# peripheral_UART.net
KiCad netlist of a schematic drawn in Altium Designer
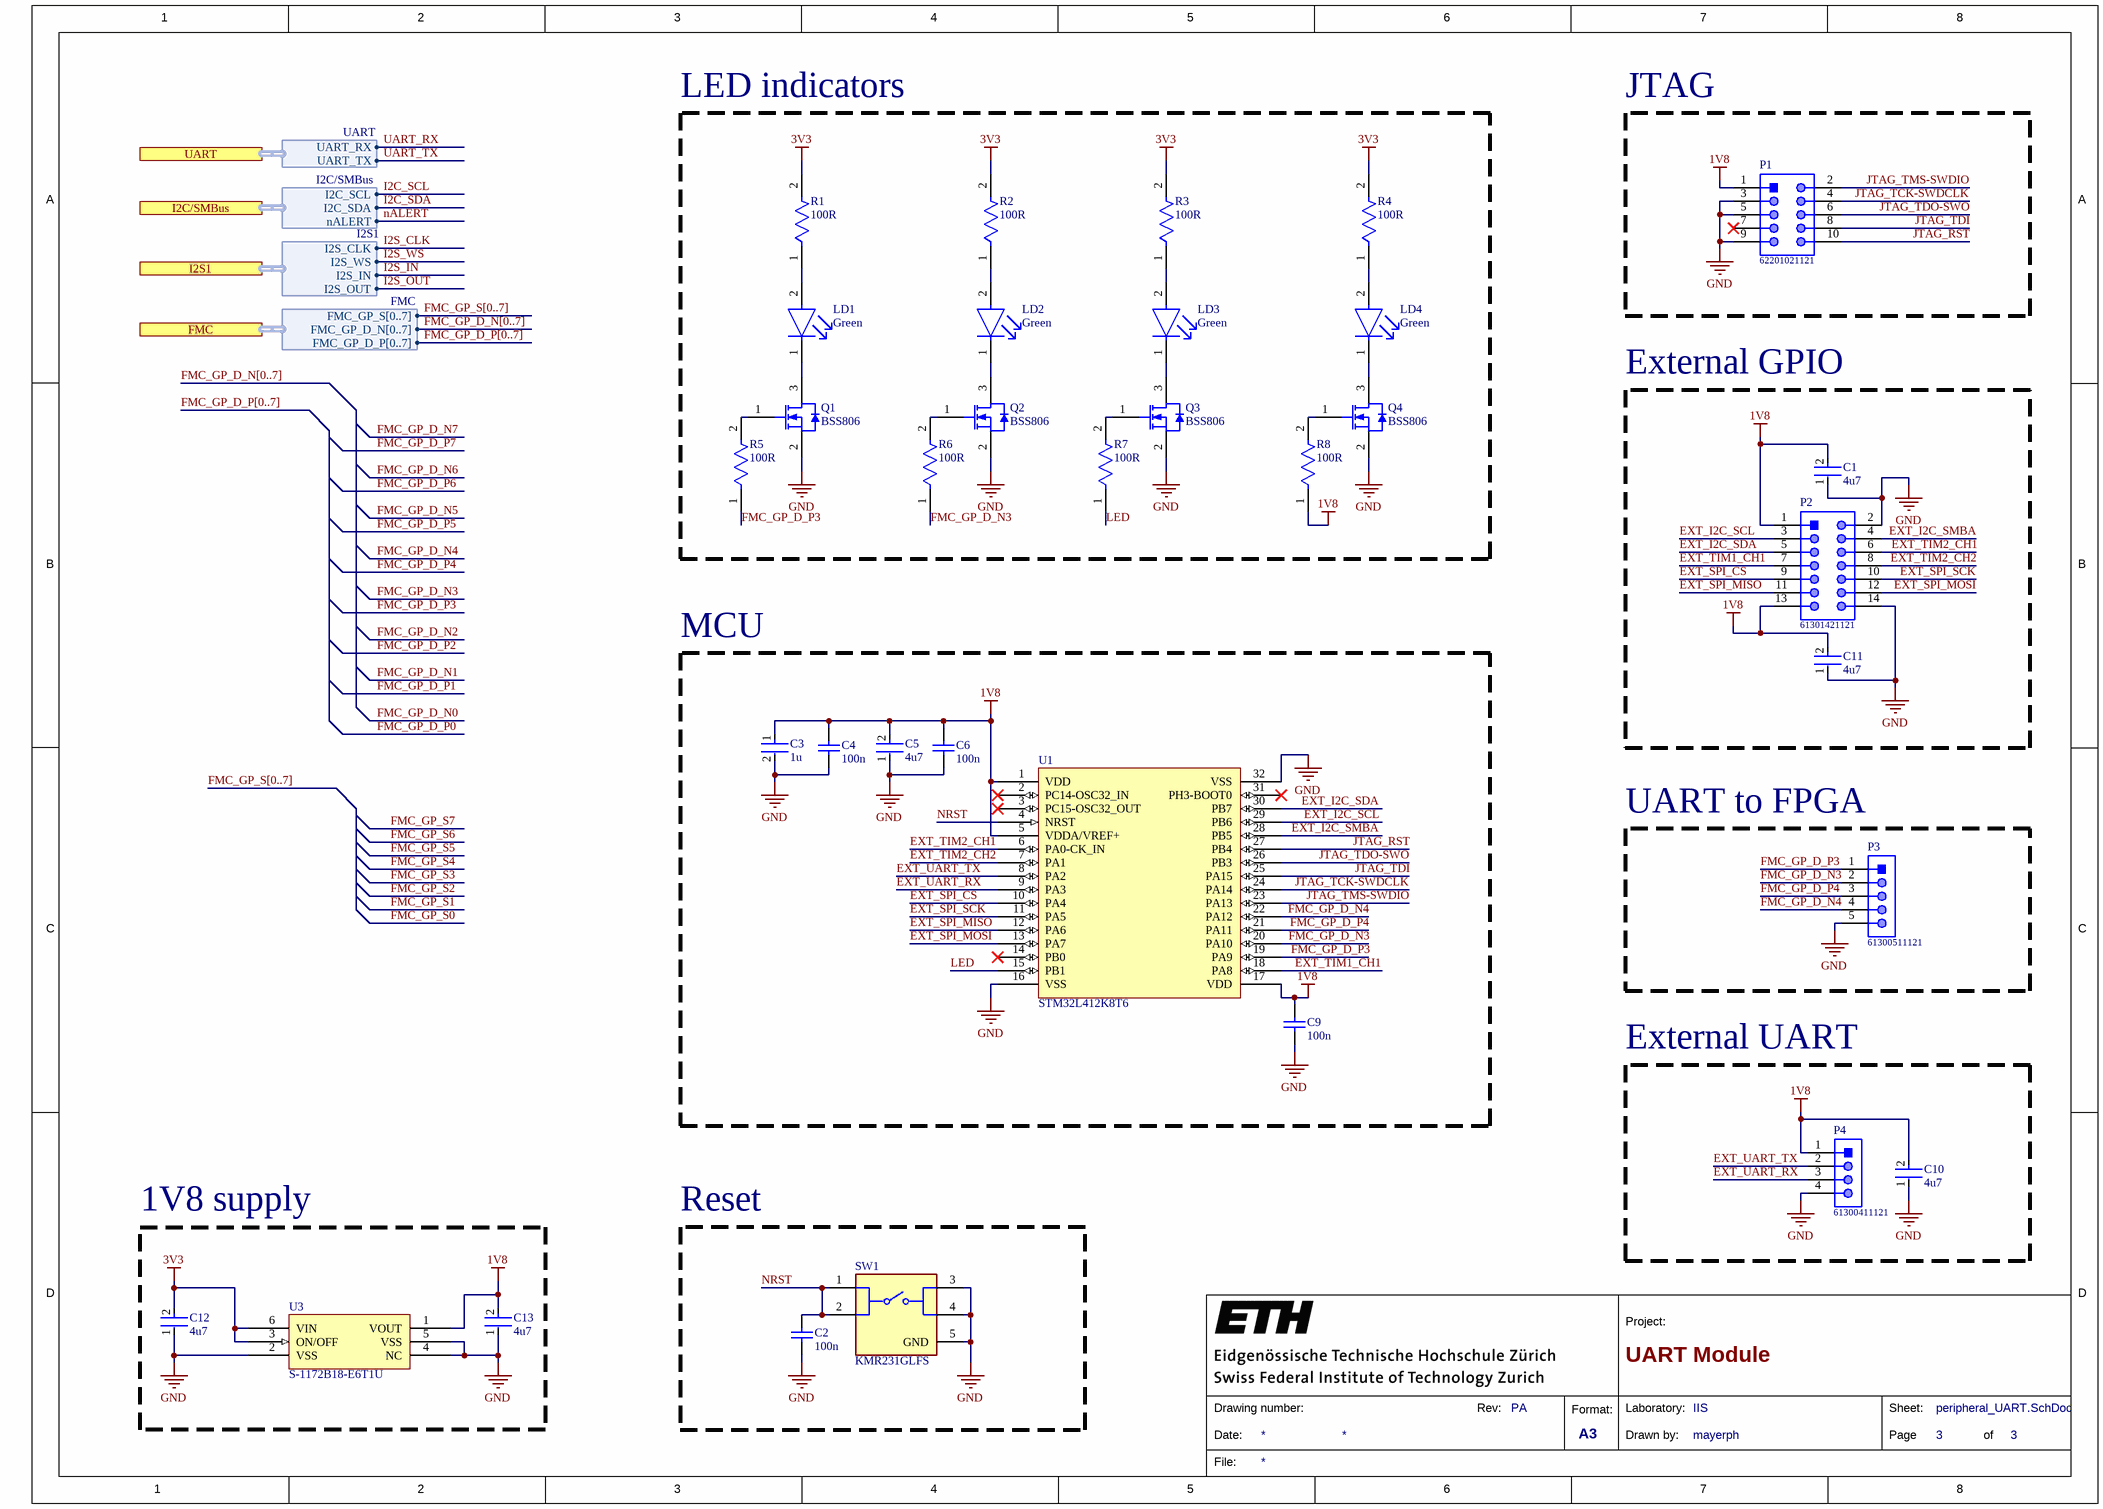
[diagram p0: peripheral_UART.SchDoc]

(export (version "E")
  (design (tool "Eeschema 10.0.6"))
  (components
    (comp (ref "C1")
      (value "4u7")
      (footprint "FP-C1608-080-0_1-IPC_C")
      (description "Multilayer Ceramic Capacitors 4.7μF ±10% 16V X7R SMD 0603")
      (fields (field (name "TOLERANCE") "10%") (field (name "VOLTAGE") "16V"))
      (libsource (lib "Altium Content Vault") (part "236180d848d6139a670b325ea6854c9"))
    )
    (comp (ref "C2")
      (value "100n")
      (footprint "CAPC1608X90X35ML15T15")
      (description "Multilayer Ceramic Capacitors 100nF ±10% 16V X7R SMD 0603")
      (fields (field (name "MANUFACTURER") "KEMET") (field (name "PART NUMBER") "0603YC104KAZ2A"))
      (libsource (lib "Altium Content Vault") (part "CAP"))
    )
    (comp (ref "C3")
      (value "1u")
      (footprint "FP-CL10B105KO8NNNC-MFG")
      (description "Multilayer Ceramic Capacitors 1μF ±10% 16V X7R SMD 0603")
      (fields
        (field (name "OCTOPART") "https://octopart.com/cl10b105ko8nnnc-samsung-19018973")
        (field (name "MANUFACTURER") "KEMET")
      )
      (libsource (lib "Altium Content Vault") (part "b4654b650e69147ec39a6b967a45e02"))
    )
    (comp (ref "C4")
      (value "100n")
      (footprint "CAPC1608X90X35ML15T15")
      (description "Multilayer Ceramic Capacitors 100nF ±10% 16V X7R SMD 0603")
      (fields (field (name "MANUFACTURER") "KEMET") (field (name "PART NUMBER") "0603YC104KAZ2A"))
      (libsource (lib "Altium Content Vault") (part "CAP"))
    )
    (comp (ref "C5")
      (value "4u7")
      (footprint "FP-C1608-080-0_1-IPC_C")
      (description "Multilayer Ceramic Capacitors 4.7μF ±10% 16V X7R SMD 0603")
      (fields (field (name "TOLERANCE") "10%") (field (name "VOLTAGE") "16V"))
      (libsource (lib "Altium Content Vault") (part "236180d848d6139a670b325ea6854c9"))
    )
    (comp (ref "C6")
      (value "100n")
      (footprint "CAPC1608X90X35ML15T15")
      (description "Multilayer Ceramic Capacitors 100nF ±10% 16V X7R SMD 0603")
      (fields (field (name "MANUFACTURER") "KEMET") (field (name "PART NUMBER") "0603YC104KAZ2A"))
      (libsource (lib "Altium Content Vault") (part "CAP"))
    )
    (comp (ref "C9")
      (value "100n")
      (footprint "CAPC1608X90X35ML15T15")
      (description "Multilayer Ceramic Capacitors 100nF ±10% 16V X7R SMD 0603")
      (fields (field (name "MANUFACTURER") "KEMET") (field (name "PART NUMBER") "0603YC104KAZ2A"))
      (libsource (lib "Altium Content Vault") (part "CAP"))
    )
    (comp (ref "C10")
      (value "4u7")
      (footprint "FP-C1608-080-0_1-IPC_C")
      (description "Multilayer Ceramic Capacitors 4.7μF ±10% 16V X7R SMD 0603")
      (fields (field (name "TOLERANCE") "10%") (field (name "VOLTAGE") "16V"))
      (libsource (lib "Altium Content Vault") (part "236180d848d6139a670b325ea6854c9"))
    )
    (comp (ref "C11")
      (value "4u7")
      (footprint "FP-C1608-080-0_1-IPC_C")
      (description "Multilayer Ceramic Capacitors 4.7μF ±10% 16V X7R SMD 0603")
      (fields (field (name "TOLERANCE") "10%") (field (name "VOLTAGE") "16V"))
      (libsource (lib "Altium Content Vault") (part "236180d848d6139a670b325ea6854c9"))
    )
    (comp (ref "C12")
      (value "4u7")
      (footprint "FP-C1608-080-0_1-IPC_C")
      (description "Multilayer Ceramic Capacitors 4.7μF ±10% 16V X7R SMD 0603")
      (fields (field (name "TOLERANCE") "10%") (field (name "VOLTAGE") "16V"))
      (libsource (lib "Altium Content Vault") (part "236180d848d6139a670b325ea6854c9"))
    )
    (comp (ref "C13")
      (value "4u7")
      (footprint "FP-C1608-080-0_1-IPC_C")
      (description "Multilayer Ceramic Capacitors 4.7μF ±10% 16V X7R SMD 0603")
      (fields (field (name "TOLERANCE") "10%") (field (name "VOLTAGE") "16V"))
      (libsource (lib "Altium Content Vault") (part "236180d848d6139a670b325ea6854c9"))
    )
    (comp (ref "LD1")
      (value "Green")
      (footprint "FP-150060VS75000-MFG")
      (description "LED GREEN CLEAR 0603 SMD")
      (fields (field (name "MANUFACTURER") "Wurth Elektronik"))
      (libsource (lib "Altium Content Vault") (part "8706943c75ba83719d021d2fdc84c58"))
    )
    (comp (ref "LD2")
      (value "Green")
      (footprint "FP-150060VS75000-MFG")
      (description "LED GREEN CLEAR 0603 SMD")
      (fields (field (name "MANUFACTURER") "Wurth Elektronik"))
      (libsource (lib "Altium Content Vault") (part "8706943c75ba83719d021d2fdc84c58"))
    )
    (comp (ref "LD3")
      (value "Green")
      (footprint "FP-150060VS75000-MFG")
      (description "LED GREEN CLEAR 0603 SMD")
      (fields (field (name "MANUFACTURER") "Wurth Elektronik"))
      (libsource (lib "Altium Content Vault") (part "8706943c75ba83719d021d2fdc84c58"))
    )
    (comp (ref "LD4")
      (value "Green")
      (footprint "FP-150060VS75000-MFG")
      (description "LED GREEN CLEAR 0603 SMD")
      (fields (field (name "MANUFACTURER") "Wurth Elektronik"))
      (libsource (lib "Altium Content Vault") (part "8706943c75ba83719d021d2fdc84c58"))
    )
    (comp (ref "P1")
      (value "${~{P}N}")
      (footprint "62201021121")
      (description "THT Vertical Pin Header WR-PHD, Pitch 1.27 mm, Dual Row, 10 pins")
      (fields
        (field (name "MANUFACTURER") "Wurth Elektronik")
        (field (name "PART NUMBER") "62201021121")
        (field (name "PUBLISHER") "WurthElektronik")
      )
      (libsource (lib "Altium Content Vault") (part "WE-CN-2P-M-R10"))
    )
    (comp (ref "P2")
      (value "${~{P}N}")
      (footprint "61301421121")
      (description "THT Vertical Pin Header WR-PHD, Pitch 2.54 mm, Dual Row, 14 pins")
      (fields
        (field (name "PART NUMBER") "61301421121")
        (field (name "MANUFACTURER") "Wurth Elektronik")
        (field (name "PUBLISHER") "WurthElektronik")
      )
      (libsource (lib "Altium Content Vault") (part "WE-CN-2P-M-R14"))
    )
    (comp (ref "P3")
      (value "${~{P}N}")
      (footprint "61300511121")
      (description "THT Vertical Pin Header WR-PHD, Pitch 2.54 mm, Single Row, 5 pins")
      (fields
        (field (name "PART NUMBER") "61300511121")
        (field (name "MANUFACTURER") "Wurth Elektronik")
        (field (name "PUBLISHER") "WurthElektronik")
      )
      (libsource (lib "Altium Content Vault") (part "WE-CN-1P-M-R5"))
    )
    (comp (ref "P4")
      (value "${~{P}N}")
      (footprint "61300411121")
      (description "THT Vertical Pin Header WR-PHD, Pitch 2.54 mm, Single Row, 4 pins")
      (fields
        (field (name "MANUFACTURER") "Wurth Elektronik")
        (field (name "PART NUMBER") "61300411121")
        (field (name "PUBLISHER") "WurthElektronik")
      )
      (libsource (lib "Altium Content Vault") (part "WE-CN-1P-M-R4"))
    )
    (comp (ref "Q1")
      (value "BSS806")
      (footprint "FAIR-SSOT3L-3_V")
      (description "MOSFET N-CH 20V 2.3A SOT23-3")
      (fields (field (name "MANUFACTURER") "Infineon Technologies"))
      (libsource (lib "Altium Content Vault") (part "NEMOS-GSD-3"))
    )
    (comp (ref "Q2")
      (value "BSS806")
      (footprint "FAIR-SSOT3L-3_V")
      (description "MOSFET N-CH 20V 2.3A SOT23-3")
      (fields (field (name "MANUFACTURER") "Infineon Technologies"))
      (libsource (lib "Altium Content Vault") (part "NEMOS-GSD-3"))
    )
    (comp (ref "Q3")
      (value "BSS806")
      (footprint "FAIR-SSOT3L-3_V")
      (description "MOSFET N-CH 20V 2.3A SOT23-3")
      (fields (field (name "MANUFACTURER") "Infineon Technologies"))
      (libsource (lib "Altium Content Vault") (part "NEMOS-GSD-3"))
    )
    (comp (ref "Q4")
      (value "BSS806")
      (footprint "FAIR-SSOT3L-3_V")
      (description "MOSFET N-CH 20V 2.3A SOT23-3")
      (fields (field (name "MANUFACTURER") "Infineon Technologies"))
      (libsource (lib "Altium Content Vault") (part "NEMOS-GSD-3"))
    )
    (comp (ref "R1")
      (value "100R")
      (footprint "FP-CRCW0603-e3-IPC_B")
      (description "RES Thick Film, 100Ω, 5%, 0.1W, 200ppm/°C, 0603")
      (fields (field (name "TOLERANCE") "5%") (field (name "MANUFACTURER") "Panasonic Electronic Components"))
      (libsource (lib "Altium Content Vault") (part "1029c3af85768c4190bb7ad29bc67b5"))
    )
    (comp (ref "R2")
      (value "100R")
      (footprint "FP-CRCW0603-e3-IPC_B")
      (description "RES Thick Film, 100Ω, 5%, 0.1W, 200ppm/°C, 0603")
      (fields (field (name "TOLERANCE") "5%") (field (name "MANUFACTURER") "Panasonic Electronic Components"))
      (libsource (lib "Altium Content Vault") (part "1029c3af85768c4190bb7ad29bc67b5"))
    )
    (comp (ref "R3")
      (value "100R")
      (footprint "FP-CRCW0603-e3-IPC_B")
      (description "RES Thick Film, 100Ω, 5%, 0.1W, 200ppm/°C, 0603")
      (fields (field (name "TOLERANCE") "5%") (field (name "MANUFACTURER") "Panasonic Electronic Components"))
      (libsource (lib "Altium Content Vault") (part "1029c3af85768c4190bb7ad29bc67b5"))
    )
    (comp (ref "R4")
      (value "100R")
      (footprint "FP-CRCW0603-e3-IPC_B")
      (description "RES Thick Film, 100Ω, 5%, 0.1W, 200ppm/°C, 0603")
      (fields (field (name "TOLERANCE") "5%") (field (name "MANUFACTURER") "Panasonic Electronic Components"))
      (libsource (lib "Altium Content Vault") (part "1029c3af85768c4190bb7ad29bc67b5"))
    )
    (comp (ref "R5")
      (value "100R")
      (footprint "FP-CRCW0603-e3-IPC_B")
      (description "RES Thick Film, 100Ω, 5%, 0.1W, 200ppm/°C, 0603")
      (fields (field (name "TOLERANCE") "5%") (field (name "MANUFACTURER") "Panasonic Electronic Components"))
      (libsource (lib "Altium Content Vault") (part "1029c3af85768c4190bb7ad29bc67b5"))
    )
    (comp (ref "R6")
      (value "100R")
      (footprint "FP-CRCW0603-e3-IPC_B")
      (description "RES Thick Film, 100Ω, 5%, 0.1W, 200ppm/°C, 0603")
      (fields (field (name "TOLERANCE") "5%") (field (name "MANUFACTURER") "Panasonic Electronic Components"))
      (libsource (lib "Altium Content Vault") (part "1029c3af85768c4190bb7ad29bc67b5"))
    )
    (comp (ref "R7")
      (value "100R")
      (footprint "FP-CRCW0603-e3-IPC_B")
      (description "RES Thick Film, 100Ω, 5%, 0.1W, 200ppm/°C, 0603")
      (fields (field (name "TOLERANCE") "5%") (field (name "MANUFACTURER") "Panasonic Electronic Components"))
      (libsource (lib "Altium Content Vault") (part "1029c3af85768c4190bb7ad29bc67b5"))
    )
    (comp (ref "R8")
      (value "100R")
      (footprint "FP-CRCW0603-e3-IPC_B")
      (description "RES Thick Film, 100Ω, 5%, 0.1W, 200ppm/°C, 0603")
      (fields (field (name "TOLERANCE") "5%") (field (name "MANUFACTURER") "Panasonic Electronic Components"))
      (libsource (lib "Altium Content Vault") (part "1029c3af85768c4190bb7ad29bc67b5"))
    )
    (comp (ref "SW1")
      (value "${~{P}N}")
      (footprint "FP-KMR231GLFS-MFG")
      (description "SWITCH TACTILE SPST-NO 0.05A 32V")
      (fields (field (name "MANUFACTURER") "C&K"))
      (libsource (lib "Altium Content Vault") (part "4ba73034ab40b7b0ce053ff7ec1e5b4"))
    )
    (comp (ref "U1")
      (value "${~{P}N}")
      (footprint "STM32L412K8T6:STM32L412K8T6")
      (description "MCU 32-bit")
      (fields (field (name "MANUFACTURER") "STMicroelectronics"))
      (libsource (lib "UART_Module") (part "STM32L412K8T6"))
    )
    (comp (ref "U3")
      (value "${~{P}N}")
      (footprint "S1172")
      (description "LDO 1V8 fixed")
      (fields (field (name "MANUFACTURER") "ABLIC Inc."))
      (libsource (lib "UART_Module") (part "S1172"))
    )
  )
  (nets
    (net (code "5") (name "/EXT_I2C_SCL") (class "Default")
      (node (ref "P2") (pin "3") (pinfunction "3_3") (pintype "passive"))
      (node (ref "U1") (pin "29") (pinfunction "PB6_29") (pintype "bidirectional"))
    )
    (net (code "6") (name "/EXT_I2C_SDA") (class "Default")
      (node (ref "P2") (pin "5") (pinfunction "5_5") (pintype "passive"))
      (node (ref "U1") (pin "30") (pinfunction "PB7_30") (pintype "bidirectional"))
    )
    (net (code "7") (name "/EXT_I2C_SMBA") (class "Default")
      (node (ref "P2") (pin "4") (pinfunction "4_4") (pintype "passive"))
      (node (ref "U1") (pin "28") (pinfunction "PB5_28") (pintype "bidirectional"))
    )
    (net (code "8") (name "/EXT_SPI_CS") (class "Default")
      (node (ref "P2") (pin "9") (pinfunction "9_9") (pintype "passive"))
      (node (ref "U1") (pin "10") (pinfunction "PA4_10") (pintype "bidirectional"))
    )
    (net (code "9") (name "/EXT_SPI_MISO") (class "Default")
      (node (ref "P2") (pin "11") (pinfunction "11_11") (pintype "passive"))
      (node (ref "U1") (pin "12") (pinfunction "PA6_12") (pintype "bidirectional"))
    )
    (net (code "10") (name "/EXT_SPI_MOSI") (class "Default")
      (node (ref "P2") (pin "12") (pinfunction "12_12") (pintype "passive"))
      (node (ref "U1") (pin "13") (pinfunction "PA7_13") (pintype "bidirectional"))
    )
    (net (code "11") (name "/EXT_SPI_SCK") (class "Default")
      (node (ref "P2") (pin "10") (pinfunction "10_10") (pintype "passive"))
      (node (ref "U1") (pin "11") (pinfunction "PA5_11") (pintype "bidirectional"))
    )
    (net (code "12") (name "/EXT_TIM1_CH1") (class "Default")
      (node (ref "P2") (pin "7") (pinfunction "7_7") (pintype "passive"))
      (node (ref "U1") (pin "18") (pinfunction "PA8_18") (pintype "bidirectional"))
    )
    (net (code "13") (name "/EXT_TIM2_CH1") (class "Default")
      (node (ref "P2") (pin "6") (pinfunction "6_6") (pintype "passive"))
      (node (ref "U1") (pin "6") (pinfunction "PA0-CK_IN_6") (pintype "bidirectional"))
    )
    (net (code "14") (name "/EXT_TIM2_CH2") (class "Default")
      (node (ref "P2") (pin "8") (pinfunction "8_8") (pintype "passive"))
      (node (ref "U1") (pin "7") (pinfunction "PA1_7") (pintype "bidirectional"))
    )
    (net (code "15") (name "/EXT_UART_RX") (class "Default")
      (node (ref "P4") (pin "3") (pinfunction "3_3") (pintype "passive"))
      (node (ref "U1") (pin "9") (pinfunction "PA3_9") (pintype "bidirectional"))
    )
    (net (code "16") (name "/EXT_UART_TX") (class "Default")
      (node (ref "P4") (pin "2") (pinfunction "2_2") (pintype "passive"))
      (node (ref "U1") (pin "8") (pinfunction "PA2_8") (pintype "bidirectional"))
    )
    (net (code "20") (name "/FMC_GP_D_N3") (class "Default")
      (node (ref "P3") (pin "2") (pinfunction "2_2") (pintype "passive"))
      (node (ref "R6") (pin "1") (pinfunction "1_1") (pintype "passive"))
      (node (ref "U1") (pin "20") (pinfunction "PA10_20") (pintype "bidirectional"))
    )
    (net (code "21") (name "/FMC_GP_D_N4") (class "Default")
      (node (ref "P3") (pin "4") (pinfunction "4_4") (pintype "passive"))
      (node (ref "U1") (pin "22") (pinfunction "PA12_22") (pintype "bidirectional"))
    )
    (net (code "29") (name "/FMC_GP_D_P3") (class "Default")
      (node (ref "P3") (pin "1") (pinfunction "1_1") (pintype "passive"))
      (node (ref "R5") (pin "1") (pinfunction "1_1") (pintype "passive"))
      (node (ref "U1") (pin "19") (pinfunction "PA9_19") (pintype "bidirectional"))
    )
    (net (code "30") (name "/FMC_GP_D_P4") (class "Default")
      (node (ref "P3") (pin "3") (pinfunction "3_3") (pintype "passive"))
      (node (ref "U1") (pin "21") (pinfunction "PA11_21") (pintype "bidirectional"))
    )
    (net (code "51") (name "/JTAG_RST") (class "Default")
      (node (ref "P1") (pin "10") (pinfunction "10_10") (pintype "passive"))
      (node (ref "U1") (pin "27") (pinfunction "PB4_27") (pintype "bidirectional"))
    )
    (net (code "52") (name "/JTAG_TCK-SWDCLK") (class "Default")
      (node (ref "P1") (pin "4") (pinfunction "4_4") (pintype "passive"))
      (node (ref "U1") (pin "24") (pinfunction "PA14_24") (pintype "bidirectional"))
    )
    (net (code "53") (name "/JTAG_TDI") (class "Default")
      (node (ref "P1") (pin "8") (pinfunction "8_8") (pintype "passive"))
      (node (ref "U1") (pin "25") (pinfunction "PA15_25") (pintype "bidirectional"))
    )
    (net (code "54") (name "/JTAG_TDO-SWO") (class "Default")
      (node (ref "P1") (pin "6") (pinfunction "6_6") (pintype "passive"))
      (node (ref "U1") (pin "26") (pinfunction "PB3_26") (pintype "bidirectional"))
    )
    (net (code "55") (name "/JTAG_TMS-SWDIO") (class "Default")
      (node (ref "P1") (pin "2") (pinfunction "2_2") (pintype "passive"))
      (node (ref "U1") (pin "23") (pinfunction "PA13_23") (pintype "bidirectional"))
    )
    (net (code "56") (name "/LED") (class "Default")
      (node (ref "R7") (pin "1") (pinfunction "1_1") (pintype "passive"))
      (node (ref "U1") (pin "15") (pinfunction "PB1_15") (pintype "bidirectional"))
    )
    (net (code "57") (name "/NRST") (class "Default")
      (node (ref "C2") (pin "2") (pinfunction "2_2") (pintype "passive"))
      (node (ref "SW1") (pin "1") (pinfunction "1_1") (pintype "passive"))
      (node (ref "SW1") (pin "2") (pinfunction "2_2") (pintype "passive"))
      (node (ref "U1") (pin "4") (pinfunction "NRST_4") (pintype "input"))
    )
    (net (code "64") (name "1V8") (class "Default")
      (node (ref "C1") (pin "2") (pinfunction "2_2") (pintype "passive"))
      (node (ref "C10") (pin "2") (pinfunction "2_2") (pintype "passive"))
      (node (ref "C11") (pin "2") (pinfunction "2_2") (pintype "passive"))
      (node (ref "C13") (pin "2") (pinfunction "2_2") (pintype "passive"))
      (node (ref "C3") (pin "1") (pinfunction "1_1") (pintype "passive"))
      (node (ref "C4") (pin "2") (pinfunction "2_2") (pintype "passive"))
      (node (ref "C5") (pin "2") (pinfunction "2_2") (pintype "passive"))
      (node (ref "C6") (pin "2") (pinfunction "2_2") (pintype "passive"))
      (node (ref "C9") (pin "2") (pinfunction "2_2") (pintype "passive"))
      (node (ref "P1") (pin "1") (pinfunction "1_1") (pintype "passive"))
      (node (ref "P2") (pin "1") (pinfunction "1_1") (pintype "passive"))
      (node (ref "P2") (pin "13") (pinfunction "13_13") (pintype "passive"))
      (node (ref "P4") (pin "1") (pinfunction "1_1") (pintype "passive"))
      (node (ref "R8") (pin "1") (pinfunction "1_1") (pintype "passive"))
      (node (ref "U1") (pin "1") (pinfunction "VDD_1") (pintype "power_in"))
      (node (ref "U1") (pin "17") (pinfunction "VDD_17") (pintype "power_in"))
      (node (ref "U1") (pin "5") (pinfunction "VDDA/VREF+_5") (pintype "power_in"))
      (node (ref "U3") (pin "1") (pinfunction "VOUT_1") (pintype "power_in"))
    )
    (net (code "65") (name "3V3") (class "Default")
      (node (ref "C12") (pin "2") (pinfunction "2_2") (pintype "passive"))
      (node (ref "R1") (pin "2") (pinfunction "2_2") (pintype "passive"))
      (node (ref "R2") (pin "2") (pinfunction "2_2") (pintype "passive"))
      (node (ref "R3") (pin "2") (pinfunction "2_2") (pintype "passive"))
      (node (ref "R4") (pin "2") (pinfunction "2_2") (pintype "passive"))
      (node (ref "U3") (pin "3") (pinfunction "ON/OFF_3") (pintype "input"))
      (node (ref "U3") (pin "6") (pinfunction "VIN_6") (pintype "power_in"))
    )
    (net (code "66") (name "GND") (class "Default")
      (node (ref "C1") (pin "1") (pinfunction "1_1") (pintype "passive"))
      (node (ref "C10") (pin "1") (pinfunction "1_1") (pintype "passive"))
      (node (ref "C11") (pin "1") (pinfunction "1_1") (pintype "passive"))
      (node (ref "C12") (pin "1") (pinfunction "1_1") (pintype "passive"))
      (node (ref "C13") (pin "1") (pinfunction "1_1") (pintype "passive"))
      (node (ref "C2") (pin "1") (pinfunction "1_1") (pintype "passive"))
      (node (ref "C3") (pin "2") (pinfunction "2_2") (pintype "passive"))
      (node (ref "C4") (pin "1") (pinfunction "1_1") (pintype "passive"))
      (node (ref "C5") (pin "1") (pinfunction "1_1") (pintype "passive"))
      (node (ref "C6") (pin "1") (pinfunction "1_1") (pintype "passive"))
      (node (ref "C9") (pin "1") (pinfunction "1_1") (pintype "passive"))
      (node (ref "P1") (pin "3") (pinfunction "3_3") (pintype "passive"))
      (node (ref "P1") (pin "5") (pinfunction "5_5") (pintype "passive"))
      (node (ref "P1") (pin "9") (pinfunction "9_9") (pintype "passive"))
      (node (ref "P2") (pin "14") (pinfunction "14_14") (pintype "passive"))
      (node (ref "P2") (pin "2") (pinfunction "2_2") (pintype "passive"))
      (node (ref "P3") (pin "5") (pinfunction "5_5") (pintype "passive"))
      (node (ref "P4") (pin "4") (pinfunction "4_4") (pintype "passive"))
      (node (ref "Q1") (pin "2") (pinfunction "S_2") (pintype "passive"))
      (node (ref "Q2") (pin "2") (pinfunction "S_2") (pintype "passive"))
      (node (ref "Q3") (pin "2") (pinfunction "S_2") (pintype "passive"))
      (node (ref "Q4") (pin "2") (pinfunction "S_2") (pintype "passive"))
      (node (ref "SW1") (pin "3") (pinfunction "3_3") (pintype "passive"))
      (node (ref "SW1") (pin "4") (pinfunction "4_4") (pintype "passive"))
      (node (ref "SW1") (pin "5") (pinfunction "GND_5") (pintype "power_in"))
      (node (ref "U1") (pin "16") (pinfunction "VSS_16") (pintype "power_in"))
      (node (ref "U1") (pin "32") (pinfunction "VSS_32") (pintype "power_in"))
      (node (ref "U3") (pin "2") (pinfunction "VSS_2") (pintype "power_in"))
      (node (ref "U3") (pin "4") (pinfunction "NC_4") (pintype "power_in"))
      (node (ref "U3") (pin "5") (pinfunction "VSS_5") (pintype "power_in"))
    )
    (net (code "67") (name "Net-(LD1-A)") (class "Default")
      (node (ref "LD1") (pin "2") (pinfunction "A_2") (pintype "passive"))
      (node (ref "R1") (pin "1") (pinfunction "1_1") (pintype "passive"))
    )
    (net (code "68") (name "Net-(LD1-C)") (class "Default")
      (node (ref "LD1") (pin "1") (pinfunction "C_1") (pintype "passive"))
      (node (ref "Q1") (pin "3") (pinfunction "D_3") (pintype "passive"))
    )
    (net (code "69") (name "Net-(LD2-A)") (class "Default")
      (node (ref "LD2") (pin "2") (pinfunction "A_2") (pintype "passive"))
      (node (ref "R2") (pin "1") (pinfunction "1_1") (pintype "passive"))
    )
    (net (code "70") (name "Net-(LD2-C)") (class "Default")
      (node (ref "LD2") (pin "1") (pinfunction "C_1") (pintype "passive"))
      (node (ref "Q2") (pin "3") (pinfunction "D_3") (pintype "passive"))
    )
    (net (code "71") (name "Net-(LD3-A)") (class "Default")
      (node (ref "LD3") (pin "2") (pinfunction "A_2") (pintype "passive"))
      (node (ref "R3") (pin "1") (pinfunction "1_1") (pintype "passive"))
    )
    (net (code "72") (name "Net-(LD3-C)") (class "Default")
      (node (ref "LD3") (pin "1") (pinfunction "C_1") (pintype "passive"))
      (node (ref "Q3") (pin "3") (pinfunction "D_3") (pintype "passive"))
    )
    (net (code "73") (name "Net-(LD4-A)") (class "Default")
      (node (ref "LD4") (pin "2") (pinfunction "A_2") (pintype "passive"))
      (node (ref "R4") (pin "1") (pinfunction "1_1") (pintype "passive"))
    )
    (net (code "74") (name "Net-(LD4-C)") (class "Default")
      (node (ref "LD4") (pin "1") (pinfunction "C_1") (pintype "passive"))
      (node (ref "Q4") (pin "3") (pinfunction "D_3") (pintype "passive"))
    )
    (net (code "75") (name "Net-(Q1-G)") (class "Default")
      (node (ref "Q1") (pin "1") (pinfunction "G_1") (pintype "passive"))
      (node (ref "R5") (pin "2") (pinfunction "2_2") (pintype "passive"))
    )
    (net (code "76") (name "Net-(Q2-G)") (class "Default")
      (node (ref "Q2") (pin "1") (pinfunction "G_1") (pintype "passive"))
      (node (ref "R6") (pin "2") (pinfunction "2_2") (pintype "passive"))
    )
    (net (code "77") (name "Net-(Q3-G)") (class "Default")
      (node (ref "Q3") (pin "1") (pinfunction "G_1") (pintype "passive"))
      (node (ref "R7") (pin "2") (pinfunction "2_2") (pintype "passive"))
    )
    (net (code "78") (name "Net-(Q4-G)") (class "Default")
      (node (ref "Q4") (pin "1") (pinfunction "G_1") (pintype "passive"))
      (node (ref "R8") (pin "2") (pinfunction "2_2") (pintype "passive"))
    )
    (net (code "79") (name "unconnected-(P1-Pad7)") (class "Default")
      (node (ref "P1") (pin "7") (pinfunction "7_7") (pintype "passive+no_connect"))
    )
    (net (code "80") (name "unconnected-(U1-PB0-Pad14)") (class "Default")
      (node (ref "U1") (pin "14") (pinfunction "PB0_14") (pintype "bidirectional+no_connect"))
    )
    (net (code "81") (name "unconnected-(U1-PC14-OSC32_IN-Pad2)") (class "Default")
      (node (ref "U1") (pin "2") (pinfunction "PC14-OSC32_IN_2") (pintype "bidirectional+no_connect"))
    )
    (net (code "82") (name "unconnected-(U1-PC15-OSC32_OUT-Pad3)") (class "Default")
      (node (ref "U1") (pin "3") (pinfunction "PC15-OSC32_OUT_3") (pintype "bidirectional+no_connect"))
    )
    (net (code "83") (name "unconnected-(U1-PH3-BOOT0-Pad31)") (class "Default")
      (node (ref "U1") (pin "31") (pinfunction "PH3-BOOT0_31") (pintype "bidirectional+no_connect"))
    )
  )
)
